# Sheet1.net
KiCad netlist of a schematic drawn in Altium Designer
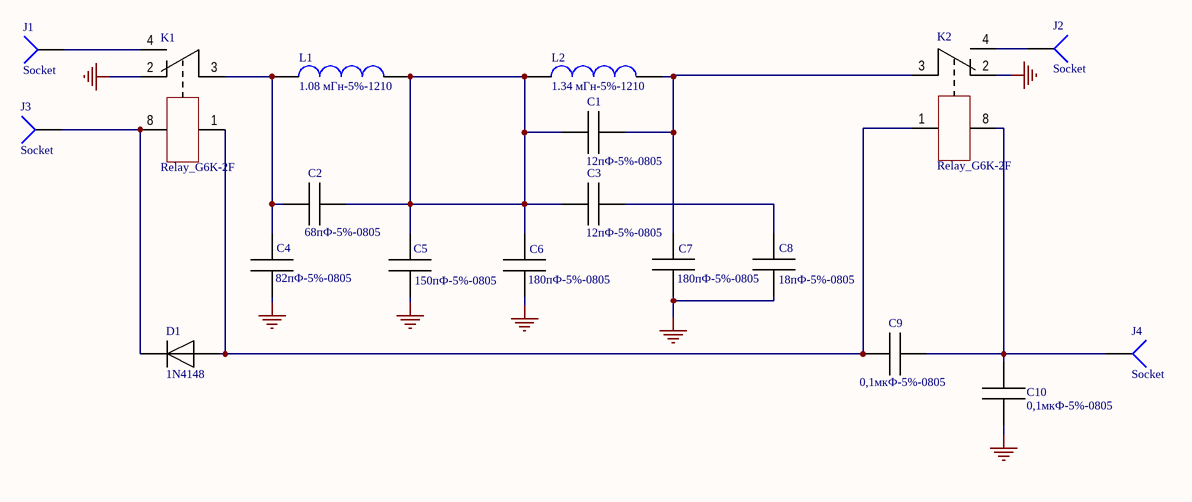
[diagram p0: Sheet1.SchDoc]

(export (version "E")
  (design (tool "Eeschema 10.0.6"))
  (components
    (comp (ref "C1")
      (value "12пФ-5%-0805")
      (footprint "Capacitor_0805")
      (fields
        (field (name "PARTNUMBER") "GRM2195C2D120JV01D")
        (field (name "MANUFACTURER") "Murata Electronics")
      )
      (libsource (lib "Schlib1_3") (part "Capasitor_0805"))
    )
    (comp (ref "C2")
      (value "68пФ-5%-0805")
      (footprint "Capacitor_0805")
      (fields
        (field (name "PARTNUMBER") "GRM2165C1H680JZ01D")
        (field (name "MANUFACTURER") "Murata Electronics")
      )
      (libsource (lib "Schlib1_3") (part "Capasitor_0805"))
    )
    (comp (ref "C3")
      (value "12пФ-5%-0805")
      (footprint "Capacitor_0805")
      (fields
        (field (name "PARTNUMBER") "GRM2195C2D120JV01D")
        (field (name "MANUFACTURER") "Murata Electronics")
      )
      (libsource (lib "Schlib1_3") (part "Capasitor_0805"))
    )
    (comp (ref "C4")
      (value "82пФ-5%-0805")
      (footprint "Capacitor_0805")
      (fields
        (field (name "PARTNUMBER") "GRM2165C1H820JZ01D")
        (field (name "MANUFACTURER") "Murata Electronics")
      )
      (libsource (lib "Schlib1_3") (part "Capasitor_0805"))
    )
    (comp (ref "C5")
      (value "150пФ-5%-0805")
      (footprint "Capacitor_0805")
      (fields
        (field (name "PARTNUMBER") "GRM2165C1H151JA01D")
        (field (name "MANUFACTURER") "Murata Electronics")
      )
      (libsource (lib "Schlib1_3") (part "Capasitor_0805"))
    )
    (comp (ref "C6")
      (value "180пФ-5%-0805")
      (footprint "Capacitor_0805")
      (fields
        (field (name "PARTNUMBER") "GRM2165C1H181JA01D")
        (field (name "MANUFACTURER") "Murata Electronics")
      )
      (libsource (lib "Schlib1_3") (part "Capasitor_0805"))
    )
    (comp (ref "C7")
      (value "180пФ-5%-0805")
      (footprint "Capacitor_0805")
      (fields
        (field (name "PARTNUMBER") "GRM2165C1H181JA01D")
        (field (name "MANUFACTURER") "Murata Electronics")
      )
      (libsource (lib "Schlib1_3") (part "Capasitor_0805"))
    )
    (comp (ref "C8")
      (value "18пФ-5%-0805")
      (footprint "Capacitor_0805")
      (fields
        (field (name "PARTNUMBER") "GRM2165C1H180JZ01D")
        (field (name "MANUFACTURER") "Murata Electronics")
      )
      (libsource (lib "Schlib1_3") (part "Capasitor_0805"))
    )
    (comp (ref "C9")
      (value "0,1мкФ-5%-0805")
      (footprint "Capacitor_0805")
      (fields
        (field (name "PARTNUMBER") "GRM21BR71E104KA01L")
        (field (name "MANUFACTURER") "Murata Electronics")
      )
      (libsource (lib "Schlib1_3") (part "Capasitor_0805"))
    )
    (comp (ref "C10")
      (value "0,1мкФ-5%-0805")
      (footprint "Capacitor_0805")
      (fields
        (field (name "PARTNUMBER") "GRM21BR71E104KA01L")
        (field (name "MANUFACTURER") "Murata Electronics")
      )
      (libsource (lib "Schlib1_3") (part "Capasitor_0805"))
    )
    (comp (ref "D1")
      (value "1N4148")
      (footprint "1N4148_MELF")
      (libsource (lib "Schlib1_3") (part "Diode_1N4148"))
    )
    (comp (ref "J1")
      (value "Socket")
      (footprint "PIN1")
      (fields (field (name "PUBLISHER") "Altium Limited"))
      (libsource (lib "Miscellaneous Connectors") (part "Socket"))
    )
    (comp (ref "J2")
      (value "Socket")
      (footprint "PIN1")
      (fields (field (name "PUBLISHER") "Altium Limited"))
      (libsource (lib "Miscellaneous Connectors") (part "Socket"))
    )
    (comp (ref "J3")
      (value "Socket")
      (footprint "PIN1")
      (fields (field (name "PUBLISHER") "Altium Limited"))
      (libsource (lib "Miscellaneous Connectors") (part "Socket"))
    )
    (comp (ref "J4")
      (value "Socket")
      (footprint "PIN1")
      (fields (field (name "PUBLISHER") "Altium Limited"))
      (libsource (lib "Miscellaneous Connectors") (part "Socket"))
    )
    (comp (ref "K1")
      (value "Relay_G6K-2F")
      (footprint "Relay_G6K-2F")
      (libsource (lib "Schlib1_3") (part "Relay_G6K-2F"))
    )
    (comp (ref "K2")
      (value "Relay_G6K-2F")
      (footprint "Relay_G6K-2F")
      (libsource (lib "") (part "Relay_G6K-2F_1"))
    )
    (comp (ref "L1")
      (value "1.08 мГн-5%-1210")
      (footprint "Inductor_1210L")
      (fields (field (name "MANUFACTURER") "TAI-TECH") (field (name "PARTNUMBER") "PASU 3225V-102J"))
      (libsource (lib "Schlib1_3") (part "Inductor_1210"))
    )
    (comp (ref "L2")
      (value "1.34 мГн-5%-1210")
      (footprint "Inductor_1210L")
      (fields (field (name "MANUFACTURER") "TAI-TECH") (field (name "PARTNUMBER") "PASU 3225V-132J"))
      (libsource (lib "Schlib1_3") (part "Inductor_1210"))
    )
  )
  (nets
    (net (code "1") (name "<NO NET>") (class "Default")
      (node (ref "C10") (pin "0") (pinfunction "0_0") (pintype "passive"))
      (node (ref "C4") (pin "0") (pinfunction "0_0") (pintype "passive"))
      (node (ref "C5") (pin "0") (pinfunction "0_0") (pintype "passive"))
      (node (ref "C6") (pin "0") (pinfunction "0_0") (pintype "passive"))
      (node (ref "C7") (pin "0") (pinfunction "0_0") (pintype "passive"))
      (node (ref "C8") (pin "0") (pinfunction "0_0") (pintype "passive"))
      (node (ref "K1") (pin "2") (pintype "passive"))
      (node (ref "K2") (pin "2") (pintype "passive"))
    )
    (net (code "2") (name "Net-(C1-Pad0)") (class "Default")
      (node (ref "C1") (pin "0") (pinfunction "0_0") (pintype "passive"))
      (node (ref "C2") (pin "1") (pinfunction "1_1") (pintype "passive"))
      (node (ref "C3") (pin "0") (pinfunction "0_0") (pintype "passive"))
      (node (ref "C5") (pin "1") (pinfunction "1_1") (pintype "passive"))
      (node (ref "C6") (pin "1") (pinfunction "1_1") (pintype "passive"))
      (node (ref "L1") (pin "2") (pinfunction "2_2") (pintype "passive"))
      (node (ref "L2") (pin "1") (pinfunction "1_1") (pintype "passive"))
    )
    (net (code "3") (name "Net-(C1-Pad1)") (class "Default")
      (node (ref "C1") (pin "1") (pinfunction "1_1") (pintype "passive"))
      (node (ref "C3") (pin "1") (pinfunction "1_1") (pintype "passive"))
      (node (ref "C7") (pin "1") (pinfunction "1_1") (pintype "passive"))
      (node (ref "C8") (pin "1") (pinfunction "1_1") (pintype "passive"))
      (node (ref "K2") (pin "3") (pintype "passive"))
      (node (ref "L2") (pin "2") (pinfunction "2_2") (pintype "passive"))
    )
    (net (code "4") (name "Net-(C2-Pad0)") (class "Default")
      (node (ref "C2") (pin "0") (pinfunction "0_0") (pintype "passive"))
      (node (ref "C4") (pin "1") (pinfunction "1_1") (pintype "passive"))
      (node (ref "K1") (pin "3") (pintype "passive"))
      (node (ref "L1") (pin "1") (pinfunction "1_1") (pintype "passive"))
    )
    (net (code "5") (name "Net-(J1-Pad1)") (class "Default")
      (node (ref "J1") (pin "1") (pinfunction "1_1") (pintype "passive"))
      (node (ref "K1") (pin "4") (pintype "passive"))
    )
    (net (code "6") (name "Net-(J2-Pad1)") (class "Default")
      (node (ref "J2") (pin "1") (pinfunction "1_1") (pintype "passive"))
      (node (ref "K2") (pin "4") (pintype "passive"))
    )
    (net (code "7") (name "Net-(K1-minus)") (class "Default")
      (node (ref "D1") (pin "2") (pinfunction "2_2") (pintype "passive"))
      (node (ref "J3") (pin "1") (pinfunction "1_1") (pintype "passive"))
      (node (ref "K1") (pin "8") (pinfunction "minus_8") (pintype "passive"))
    )
    (net (code "8") (name "Net-(K1-plus)") (class "Default")
      (node (ref "C9") (pin "0") (pinfunction "0_0") (pintype "passive"))
      (node (ref "D1") (pin "1") (pinfunction "1_1") (pintype "passive"))
      (node (ref "K1") (pin "1") (pinfunction "plus_1") (pintype "passive"))
      (node (ref "K2") (pin "1") (pinfunction "plus_1") (pintype "passive"))
    )
    (net (code "9") (name "Net-(K2-minus)") (class "Default")
      (node (ref "C10") (pin "1") (pinfunction "1_1") (pintype "passive"))
      (node (ref "C9") (pin "1") (pinfunction "1_1") (pintype "passive"))
      (node (ref "J4") (pin "1") (pinfunction "1_1") (pintype "passive"))
      (node (ref "K2") (pin "8") (pinfunction "minus_8") (pintype "passive"))
    )
  )
)
